# sensori_di_liena.net
KiCad netlist of a schematic drawn in EAGLE
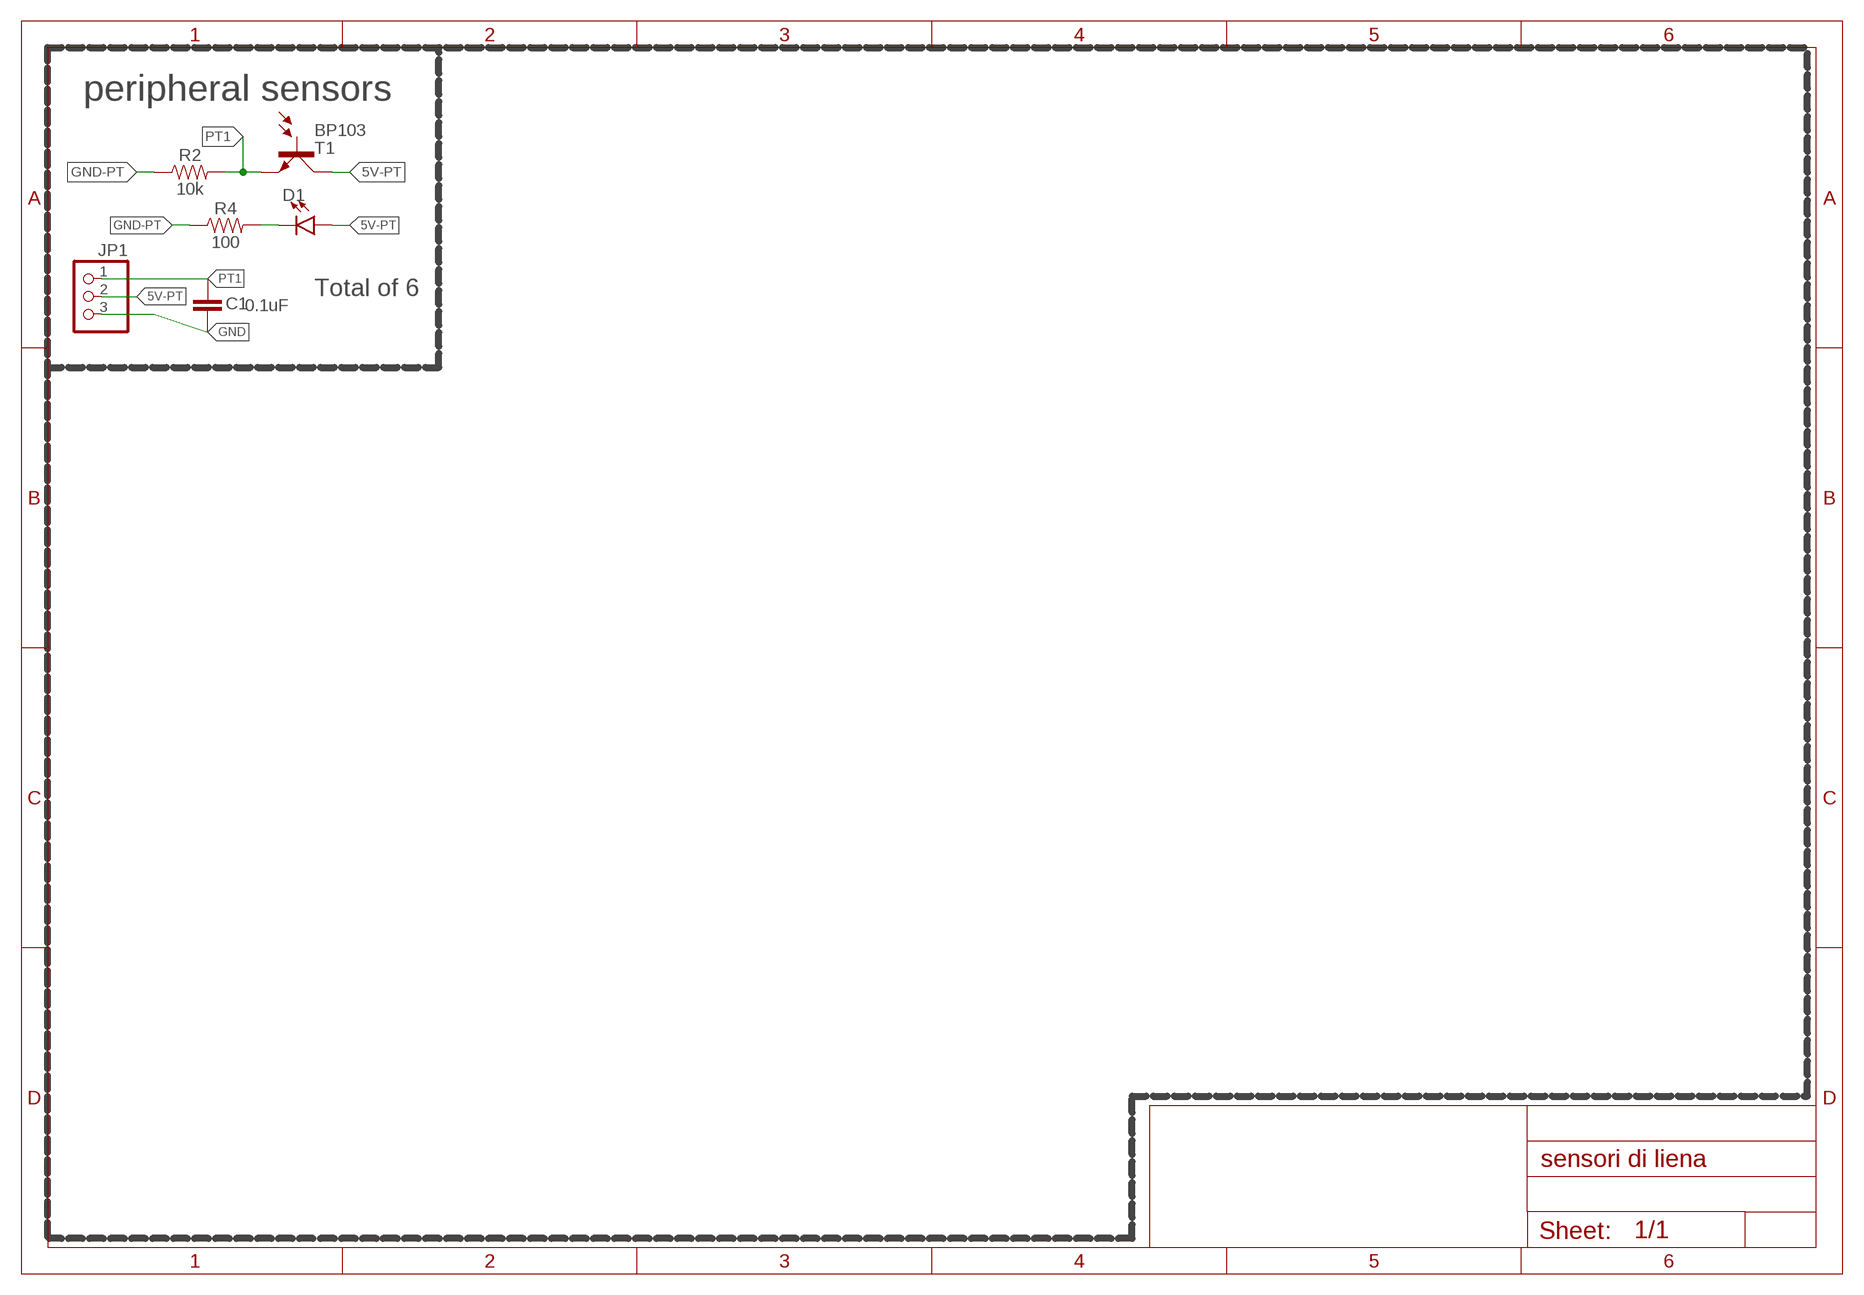
[diagram p0: schematic, sheet 1]

(export (version "E")
  (design (tool "Eeschema 10.0.6"))
  (components
    (comp (ref "C1")
      (value "0.1uF")
      (footprint "eagle-import:CAP-PTH-SMALL-KIT")
      (libsource (lib "eagle-import") (part "0.1UF-KIT-EZ-50V-20%"))
    )
    (comp (ref "D1")
      (value "LED3MM")
      (footprint "eagle-import:LED_3MM")
      (libsource (lib "eagle-import") (part "LED3MM"))
    )
    (comp (ref "JP1")
      (value "PINHD-1X3")
      (footprint "eagle-import:1X03")
      (libsource (lib "eagle-import") (part "PINHD-1X3"))
    )
    (comp (ref "R2")
      (value "10k")
      (footprint "eagle-import:0603")
      (libsource (lib "eagle-import") (part "10KOHM-0603-1/10W-1%"))
    )
    (comp (ref "R4")
      (value "100")
      (footprint "eagle-import:0603")
      (libsource (lib "eagle-import") (part "10KOHM-0603-1/10W-1%"))
    )
    (comp (ref "T1")
      (value "BP103")
      (footprint "eagle-import:BP103")
      (libsource (lib "eagle-import") (part "BP103"))
    )
  )
  (nets
    (net (code "1") (name "5V-PT") (class "Default")
      (node (ref "D1") (pin "A") (pinfunction "A_A") (pintype "passive"))
      (node (ref "JP1") (pin "2") (pinfunction "2_2") (pintype "passive"))
      (node (ref "T1") (pin "C") (pinfunction "C_C") (pintype "passive"))
    )
    (net (code "2") (name "GND") (class "Default")
      (node (ref "C1") (pin "2") (pinfunction "2_2") (pintype "passive"))
      (node (ref "JP1") (pin "3") (pinfunction "3_3") (pintype "passive"))
    )
    (net (code "3") (name "GND-PT") (class "Default")
      (node (ref "R2") (pin "1") (pinfunction "1_1") (pintype "passive"))
      (node (ref "R4") (pin "1") (pinfunction "1_1") (pintype "passive"))
    )
    (net (code "4") (name "Net-(D1-C)") (class "Default")
      (node (ref "D1") (pin "K") (pinfunction "C_K") (pintype "passive"))
      (node (ref "R4") (pin "2") (pinfunction "2_2") (pintype "passive"))
    )
    (net (code "5") (name "PT1") (class "Default")
      (node (ref "C1") (pin "1") (pinfunction "1_1") (pintype "passive"))
      (node (ref "JP1") (pin "1") (pinfunction "1_1") (pintype "passive"))
      (node (ref "R2") (pin "2") (pinfunction "2_2") (pintype "passive"))
      (node (ref "T1") (pin "E") (pinfunction "E_E") (pintype "passive"))
    )
    (net (code "6") (name "unconnected-(T1-PadB)") (class "Default")
      (node (ref "T1") (pin "B") (pinfunction "B_B") (pintype "passive"))
    )
  )
)
